# ManualMotorDriver.net
KiCad netlist of a schematic drawn in EAGLE
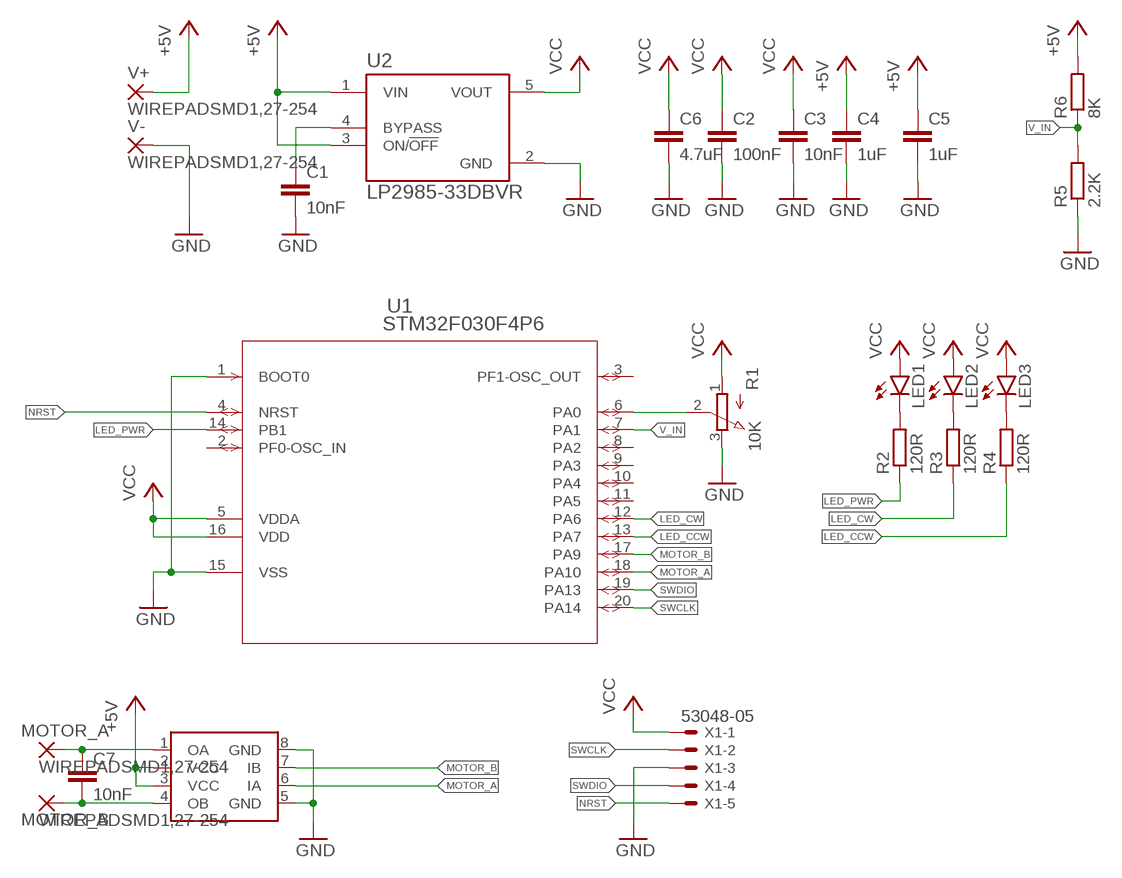
[diagram p0: schematic, sheet 1]

(export (version "E")
  (design (tool "Eeschema 10.0.6"))
  (components
    (comp (ref "C1")
      (value "10nF")
      (footprint "eagle-import:C0402K")
      (libsource (lib "eagle-import") (part "C-EUC0402K"))
    )
    (comp (ref "C2")
      (value "100nF")
      (footprint "eagle-import:C0402K")
      (libsource (lib "eagle-import") (part "C-EUC0402K"))
    )
    (comp (ref "C3")
      (value "10nF")
      (footprint "eagle-import:C0402K")
      (libsource (lib "eagle-import") (part "C-EUC0402K"))
    )
    (comp (ref "C4")
      (value "1uF")
      (footprint "eagle-import:C0402K")
      (libsource (lib "eagle-import") (part "C-EUC0402K"))
    )
    (comp (ref "C5")
      (value "1uF")
      (footprint "eagle-import:C0402K")
      (libsource (lib "eagle-import") (part "C-EUC0402K"))
    )
    (comp (ref "C6")
      (value "4.7uF")
      (footprint "eagle-import:C0805")
      (libsource (lib "eagle-import") (part "C-EUC0805"))
    )
    (comp (ref "C7")
      (value "10nF")
      (footprint "eagle-import:C0805")
      (libsource (lib "eagle-import") (part "C-EUC0805"))
    )
    (comp (ref "LED1")
      (value "LEDCHIP-LED0603")
      (footprint "eagle-import:CHIP-LED0603")
      (libsource (lib "eagle-import") (part "LEDCHIP-LED0603"))
    )
    (comp (ref "LED2")
      (value "LEDCHIP-LED0603")
      (footprint "eagle-import:CHIP-LED0603")
      (libsource (lib "eagle-import") (part "LEDCHIP-LED0603"))
    )
    (comp (ref "LED3")
      (value "LEDCHIP-LED0603")
      (footprint "eagle-import:CHIP-LED0603")
      (libsource (lib "eagle-import") (part "LEDCHIP-LED0603"))
    )
    (comp (ref "MOTOR_A")
      (value "WIREPADSMD1,27-254")
      (footprint "eagle-import:SMD1,27-2,54")
      (libsource (lib "eagle-import") (part "WIREPADSMD1,27-254"))
    )
    (comp (ref "MOTOR_B")
      (value "WIREPADSMD1,27-254")
      (footprint "eagle-import:SMD1,27-2,54")
      (libsource (lib "eagle-import") (part "WIREPADSMD1,27-254"))
    )
    (comp (ref "R1")
      (value "10K")
      (footprint "eagle-import:EVUFXL")
      (libsource (lib "eagle-import") (part "EVULF3"))
    )
    (comp (ref "R2")
      (value "120R")
      (footprint "eagle-import:R0402")
      (libsource (lib "eagle-import") (part "R-EU_R0402"))
    )
    (comp (ref "R3")
      (value "120R")
      (footprint "eagle-import:R0402")
      (libsource (lib "eagle-import") (part "R-EU_R0402"))
    )
    (comp (ref "R4")
      (value "120R")
      (footprint "eagle-import:R0402")
      (libsource (lib "eagle-import") (part "R-EU_R0402"))
    )
    (comp (ref "R5")
      (value "2.2K")
      (footprint "eagle-import:R0402")
      (libsource (lib "eagle-import") (part "R-EU_R0402"))
    )
    (comp (ref "R6")
      (value "8K")
      (footprint "eagle-import:R0402")
      (libsource (lib "eagle-import") (part "R-EU_R0402"))
    )
    (comp (ref "U1")
      (value "STM32F030F4P6")
      (footprint "eagle-import:TSSOP20")
      (fields (field (name "COPYRIGHT") "Copyright (C) 2022 Ultra Librarian. All rights reserved."))
      (libsource (lib "eagle-import") (part "STM32F030F4P6"))
    )
    (comp (ref "U2")
      (value "LP2985-33DBVR")
      (footprint "eagle-import:SOT95P280X145-5N")
      (fields (field (name "MF") "Texas Instruments"))
      (libsource (lib "eagle-import") (part "LP2985-33DBVR"))
    )
    (comp (ref "U3")
      (value "L9110SO8")
      (footprint "eagle-import:SO-08")
      (fields (field (name "MF") "Asic") (field (name "MP") "L9110 (SOP-8)"))
      (libsource (lib "eagle-import") (part "L9110SO8"))
    )
    (comp (ref "V+")
      (value "WIREPADSMD1,27-254")
      (footprint "eagle-import:SMD1,27-2,54")
      (libsource (lib "eagle-import") (part "WIREPADSMD1,27-254"))
    )
    (comp (ref "V-")
      (value "WIREPADSMD1,27-254")
      (footprint "eagle-import:SMD1,27-2,54")
      (libsource (lib "eagle-import") (part "WIREPADSMD1,27-254"))
    )
    (comp (ref "X1")
      (value "53048-05")
      (footprint "eagle-import:53048-05")
      (fields (field (name "MF") "MOLEX") (field (name "MPN") "53048-0510"))
      (libsource (lib "eagle-import") (part "53?-05048"))
    )
  )
  (nets
    (net (code "1") (name "+5V") (class "Default")
      (node (ref "C4") (pin "1") (pinfunction "1_1") (pintype "passive"))
      (node (ref "C5") (pin "1") (pinfunction "1_1") (pintype "passive"))
      (node (ref "R6") (pin "2") (pinfunction "2_2") (pintype "passive"))
      (node (ref "U2") (pin "1") (pinfunction "VIN_1") (pintype "input"))
      (node (ref "U2") (pin "3") (pinfunction "ON/~{OFF}_3") (pintype "input"))
      (node (ref "U3") (pin "2") (pinfunction "VCC_2") (pintype "power_in"))
      (node (ref "U3") (pin "3") (pinfunction "VCC_3") (pintype "power_in"))
      (node (ref "V+") (pin "1") (pinfunction "P_1") (pintype "passive"))
    )
    (net (code "2") (name "GND") (class "Default")
      (node (ref "C1") (pin "2") (pinfunction "2_2") (pintype "passive"))
      (node (ref "C2") (pin "2") (pinfunction "2_2") (pintype "passive"))
      (node (ref "C3") (pin "2") (pinfunction "2_2") (pintype "passive"))
      (node (ref "C4") (pin "2") (pinfunction "2_2") (pintype "passive"))
      (node (ref "C5") (pin "2") (pinfunction "2_2") (pintype "passive"))
      (node (ref "C6") (pin "2") (pinfunction "2_2") (pintype "passive"))
      (node (ref "R1") (pin "3") (pinfunction "E_3") (pintype "passive"))
      (node (ref "R5") (pin "1") (pinfunction "1_1") (pintype "passive"))
      (node (ref "U1") (pin "1") (pinfunction "BOOT0_1") (pintype "input"))
      (node (ref "U1") (pin "15") (pinfunction "VSS_15") (pintype "power_in"))
      (node (ref "U2") (pin "2") (pinfunction "GND_2") (pintype "power_in"))
      (node (ref "U3") (pin "5") (pinfunction "GND_5") (pintype "power_in"))
      (node (ref "U3") (pin "8") (pinfunction "GND_8") (pintype "power_in"))
      (node (ref "V-") (pin "1") (pinfunction "P_1") (pintype "passive"))
      (node (ref "X1") (pin "3") (pinfunction "S_3") (pintype "passive"))
    )
    (net (code "3") (name "LED_CCW") (class "Default")
      (node (ref "R4") (pin "1") (pinfunction "1_1") (pintype "passive"))
      (node (ref "U1") (pin "13") (pinfunction "PA7_13") (pintype "bidirectional"))
    )
    (net (code "4") (name "LED_CW") (class "Default")
      (node (ref "R3") (pin "1") (pinfunction "1_1") (pintype "passive"))
      (node (ref "U1") (pin "12") (pinfunction "PA6_12") (pintype "bidirectional"))
    )
    (net (code "5") (name "LED_PWR") (class "Default")
      (node (ref "R2") (pin "1") (pinfunction "1_1") (pintype "passive"))
      (node (ref "U1") (pin "14") (pinfunction "PB1_14") (pintype "bidirectional"))
    )
    (net (code "6") (name "MOTOR_A") (class "Default")
      (node (ref "U1") (pin "18") (pinfunction "PA10_18") (pintype "bidirectional"))
      (node (ref "U3") (pin "6") (pinfunction "IA_6") (pintype "input"))
    )
    (net (code "7") (name "MOTOR_B") (class "Default")
      (node (ref "U1") (pin "17") (pinfunction "PA9_17") (pintype "bidirectional"))
      (node (ref "U3") (pin "7") (pinfunction "IB_7") (pintype "input"))
    )
    (net (code "8") (name "NRST") (class "Default")
      (node (ref "U1") (pin "4") (pinfunction "NRST_4") (pintype "bidirectional"))
      (node (ref "X1") (pin "5") (pinfunction "S_5") (pintype "passive"))
    )
    (net (code "9") (name "Net-(LED1-PadC)") (class "Default")
      (node (ref "LED1") (pin "C") (pinfunction "C_C") (pintype "passive"))
      (node (ref "R2") (pin "2") (pinfunction "2_2") (pintype "passive"))
    )
    (net (code "10") (name "Net-(LED2-PadC)") (class "Default")
      (node (ref "LED2") (pin "C") (pinfunction "C_C") (pintype "passive"))
      (node (ref "R3") (pin "2") (pinfunction "2_2") (pintype "passive"))
    )
    (net (code "11") (name "Net-(LED3-PadC)") (class "Default")
      (node (ref "LED3") (pin "C") (pinfunction "C_C") (pintype "passive"))
      (node (ref "R4") (pin "2") (pinfunction "2_2") (pintype "passive"))
    )
    (net (code "12") (name "Net-(MOTOR_A-P)") (class "Default")
      (node (ref "C7") (pin "1") (pinfunction "1_1") (pintype "passive"))
      (node (ref "MOTOR_A") (pin "1") (pinfunction "P_1") (pintype "passive"))
      (node (ref "U3") (pin "1") (pinfunction "OA_1") (pintype "output"))
    )
    (net (code "13") (name "Net-(MOTOR_B-P)") (class "Default")
      (node (ref "C7") (pin "2") (pinfunction "2_2") (pintype "passive"))
      (node (ref "MOTOR_B") (pin "1") (pinfunction "P_1") (pintype "passive"))
      (node (ref "U3") (pin "4") (pinfunction "OB_4") (pintype "output"))
    )
    (net (code "14") (name "Net-(R1-S)") (class "Default")
      (node (ref "R1") (pin "2") (pinfunction "S_2") (pintype "passive"))
      (node (ref "U1") (pin "6") (pinfunction "PA0_6") (pintype "bidirectional"))
    )
    (net (code "15") (name "Net-(U2-BYPASS)") (class "Default")
      (node (ref "C1") (pin "1") (pinfunction "1_1") (pintype "passive"))
      (node (ref "U2") (pin "4") (pinfunction "BYPASS_4") (pintype "bidirectional"))
    )
    (net (code "16") (name "SWCLK") (class "Default")
      (node (ref "U1") (pin "20") (pinfunction "PA14_20") (pintype "bidirectional"))
      (node (ref "X1") (pin "2") (pinfunction "S_2") (pintype "passive"))
    )
    (net (code "17") (name "SWDIO") (class "Default")
      (node (ref "U1") (pin "19") (pinfunction "PA13_19") (pintype "bidirectional"))
      (node (ref "X1") (pin "4") (pinfunction "S_4") (pintype "passive"))
    )
    (net (code "18") (name "VCC") (class "Default")
      (node (ref "C2") (pin "1") (pinfunction "1_1") (pintype "passive"))
      (node (ref "C3") (pin "1") (pinfunction "1_1") (pintype "passive"))
      (node (ref "C6") (pin "1") (pinfunction "1_1") (pintype "passive"))
      (node (ref "LED1") (pin "A") (pinfunction "A_A") (pintype "passive"))
      (node (ref "LED2") (pin "A") (pinfunction "A_A") (pintype "passive"))
      (node (ref "LED3") (pin "A") (pinfunction "A_A") (pintype "passive"))
      (node (ref "R1") (pin "1") (pinfunction "A_1") (pintype "passive"))
      (node (ref "U1") (pin "16") (pinfunction "VDD_16") (pintype "power_in"))
      (node (ref "U1") (pin "5") (pinfunction "VDDA_5") (pintype "power_in"))
      (node (ref "U2") (pin "5") (pinfunction "VOUT_5") (pintype "output"))
      (node (ref "X1") (pin "1") (pinfunction "S_1") (pintype "passive"))
    )
    (net (code "19") (name "V_IN") (class "Default")
      (node (ref "R5") (pin "2") (pinfunction "2_2") (pintype "passive"))
      (node (ref "R6") (pin "1") (pinfunction "1_1") (pintype "passive"))
      (node (ref "U1") (pin "7") (pinfunction "PA1_7") (pintype "bidirectional"))
    )
    (net (code "20") (name "unconnected-(U1-PA2-Pad8)") (class "Default")
      (node (ref "U1") (pin "8") (pinfunction "PA2_8") (pintype "bidirectional"))
    )
    (net (code "21") (name "unconnected-(U1-PA3-Pad9)") (class "Default")
      (node (ref "U1") (pin "9") (pinfunction "PA3_9") (pintype "bidirectional"))
    )
    (net (code "22") (name "unconnected-(U1-PA4-Pad10)") (class "Default")
      (node (ref "U1") (pin "10") (pinfunction "PA4_10") (pintype "bidirectional"))
    )
    (net (code "23") (name "unconnected-(U1-PA5-Pad11)") (class "Default")
      (node (ref "U1") (pin "11") (pinfunction "PA5_11") (pintype "bidirectional"))
    )
    (net (code "24") (name "unconnected-(U1-PF0-OSC_IN-Pad2)") (class "Default")
      (node (ref "U1") (pin "2") (pinfunction "PF0-OSC_IN_2") (pintype "bidirectional"))
    )
    (net (code "25") (name "unconnected-(U1-PF1-OSC_OUT-Pad3)") (class "Default")
      (node (ref "U1") (pin "3") (pinfunction "PF1-OSC_OUT_3") (pintype "bidirectional"))
    )
  )
)
